# 01_Main.net
KiCad netlist of a schematic drawn in Altium Designer
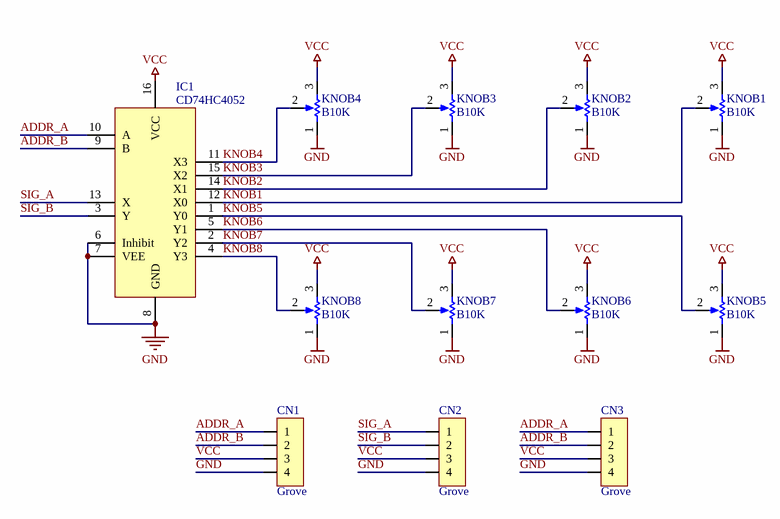
[diagram p0: 01.Main.SchDoc]

(export (version "E")
  (design (tool "Eeschema 10.0.6"))
  (components
    (comp (ref "CN1")
      (value "Grove")
      (footprint "Grove-4P-180D")
      (libsource (lib "MainnoLab library") (part "Connector 1X4"))
    )
    (comp (ref "CN2")
      (value "Grove")
      (footprint "Grove-4P-180D")
      (libsource (lib "MainnoLab library") (part "Connector 1X4"))
    )
    (comp (ref "CN3")
      (value "Grove")
      (footprint "Grove-4P-180D")
      (libsource (lib "MainnoLab library") (part "Connector 1X4"))
    )
    (comp (ref "IC1")
      (value "CD74HC4052")
      (footprint "SOIC16")
      (libsource (lib "MainnoLab library") (part "TC74HC4052AF"))
    )
    (comp (ref "KNOB1")
      (value "B10K")
      (footprint "RV09")
      (libsource (lib "Jixuan's library") (part "VR Mono"))
    )
    (comp (ref "KNOB2")
      (value "B10K")
      (footprint "RV09")
      (libsource (lib "Jixuan's library") (part "VR Mono"))
    )
    (comp (ref "KNOB3")
      (value "B10K")
      (footprint "RV09")
      (libsource (lib "Jixuan's library") (part "VR Mono"))
    )
    (comp (ref "KNOB4")
      (value "B10K")
      (footprint "RV09")
      (libsource (lib "Jixuan's library") (part "VR Mono"))
    )
    (comp (ref "KNOB5")
      (value "B10K")
      (footprint "RV09")
      (libsource (lib "Jixuan's library") (part "VR Mono"))
    )
    (comp (ref "KNOB6")
      (value "B10K")
      (footprint "RV09")
      (libsource (lib "Jixuan's library") (part "VR Mono"))
    )
    (comp (ref "KNOB7")
      (value "B10K")
      (footprint "RV09")
      (libsource (lib "Jixuan's library") (part "VR Mono"))
    )
    (comp (ref "KNOB8")
      (value "B10K")
      (footprint "RV09")
      (libsource (lib "Jixuan's library") (part "VR Mono"))
    )
  )
  (nets
    (net (code "1") (name "/ADDR_A") (class "Default")
      (node (ref "CN1") (pin "1") (pinfunction "1_1") (pintype "passive"))
      (node (ref "CN3") (pin "1") (pinfunction "1_1") (pintype "passive"))
      (node (ref "IC1") (pin "10") (pinfunction "A_10") (pintype "passive"))
    )
    (net (code "2") (name "/ADDR_B") (class "Default")
      (node (ref "CN1") (pin "2") (pinfunction "2_2") (pintype "passive"))
      (node (ref "CN3") (pin "2") (pinfunction "2_2") (pintype "passive"))
      (node (ref "IC1") (pin "9") (pinfunction "B_9") (pintype "passive"))
    )
    (net (code "3") (name "/KNOB1") (class "Default")
      (node (ref "IC1") (pin "12") (pinfunction "X0_12") (pintype "passive"))
      (node (ref "KNOB1") (pin "2") (pinfunction "2_2") (pintype "passive"))
    )
    (net (code "4") (name "/KNOB2") (class "Default")
      (node (ref "IC1") (pin "14") (pinfunction "X1_14") (pintype "passive"))
      (node (ref "KNOB2") (pin "2") (pinfunction "2_2") (pintype "passive"))
    )
    (net (code "5") (name "/KNOB3") (class "Default")
      (node (ref "IC1") (pin "15") (pinfunction "X2_15") (pintype "passive"))
      (node (ref "KNOB3") (pin "2") (pinfunction "2_2") (pintype "passive"))
    )
    (net (code "6") (name "/KNOB4") (class "Default")
      (node (ref "IC1") (pin "11") (pinfunction "X3_11") (pintype "passive"))
      (node (ref "KNOB4") (pin "2") (pinfunction "2_2") (pintype "passive"))
    )
    (net (code "7") (name "/KNOB5") (class "Default")
      (node (ref "IC1") (pin "1") (pinfunction "Y0_1") (pintype "passive"))
      (node (ref "KNOB5") (pin "2") (pinfunction "2_2") (pintype "passive"))
    )
    (net (code "8") (name "/KNOB6") (class "Default")
      (node (ref "IC1") (pin "5") (pinfunction "Y1_5") (pintype "passive"))
      (node (ref "KNOB6") (pin "2") (pinfunction "2_2") (pintype "passive"))
    )
    (net (code "9") (name "/KNOB7") (class "Default")
      (node (ref "IC1") (pin "2") (pinfunction "Y2_2") (pintype "passive"))
      (node (ref "KNOB7") (pin "2") (pinfunction "2_2") (pintype "passive"))
    )
    (net (code "10") (name "/KNOB8") (class "Default")
      (node (ref "IC1") (pin "4") (pinfunction "Y3_4") (pintype "passive"))
      (node (ref "KNOB8") (pin "2") (pinfunction "2_2") (pintype "passive"))
    )
    (net (code "11") (name "/SIG_A") (class "Default")
      (node (ref "CN2") (pin "1") (pinfunction "1_1") (pintype "passive"))
      (node (ref "IC1") (pin "13") (pinfunction "X_13") (pintype "passive"))
    )
    (net (code "12") (name "/SIG_B") (class "Default")
      (node (ref "CN2") (pin "2") (pinfunction "2_2") (pintype "passive"))
      (node (ref "IC1") (pin "3") (pinfunction "Y_3") (pintype "passive"))
    )
    (net (code "13") (name "GND") (class "Default")
      (node (ref "CN1") (pin "4") (pinfunction "4_4") (pintype "passive"))
      (node (ref "CN2") (pin "4") (pinfunction "4_4") (pintype "passive"))
      (node (ref "CN3") (pin "4") (pinfunction "4_4") (pintype "passive"))
      (node (ref "IC1") (pin "6") (pinfunction "Inhibit_6") (pintype "passive"))
      (node (ref "IC1") (pin "7") (pinfunction "VEE_7") (pintype "passive"))
      (node (ref "IC1") (pin "8") (pinfunction "GND_8") (pintype "passive"))
      (node (ref "KNOB1") (pin "1") (pinfunction "1_1") (pintype "passive"))
      (node (ref "KNOB2") (pin "1") (pinfunction "1_1") (pintype "passive"))
      (node (ref "KNOB3") (pin "1") (pinfunction "1_1") (pintype "passive"))
      (node (ref "KNOB4") (pin "1") (pinfunction "1_1") (pintype "passive"))
      (node (ref "KNOB5") (pin "1") (pinfunction "1_1") (pintype "passive"))
      (node (ref "KNOB6") (pin "1") (pinfunction "1_1") (pintype "passive"))
      (node (ref "KNOB7") (pin "1") (pinfunction "1_1") (pintype "passive"))
      (node (ref "KNOB8") (pin "1") (pinfunction "1_1") (pintype "passive"))
    )
    (net (code "14") (name "VCC") (class "Default")
      (node (ref "CN1") (pin "3") (pinfunction "3_3") (pintype "passive"))
      (node (ref "CN2") (pin "3") (pinfunction "3_3") (pintype "passive"))
      (node (ref "CN3") (pin "3") (pinfunction "3_3") (pintype "passive"))
      (node (ref "IC1") (pin "16") (pinfunction "VCC_16") (pintype "passive"))
      (node (ref "KNOB1") (pin "3") (pinfunction "3_3") (pintype "passive"))
      (node (ref "KNOB2") (pin "3") (pinfunction "3_3") (pintype "passive"))
      (node (ref "KNOB3") (pin "3") (pinfunction "3_3") (pintype "passive"))
      (node (ref "KNOB4") (pin "3") (pinfunction "3_3") (pintype "passive"))
      (node (ref "KNOB5") (pin "3") (pinfunction "3_3") (pintype "passive"))
      (node (ref "KNOB6") (pin "3") (pinfunction "3_3") (pintype "passive"))
      (node (ref "KNOB7") (pin "3") (pinfunction "3_3") (pintype "passive"))
      (node (ref "KNOB8") (pin "3") (pinfunction "3_3") (pintype "passive"))
    )
  )
)
